# untitled.net
KiCad netlist of a schematic drawn in EAGLE
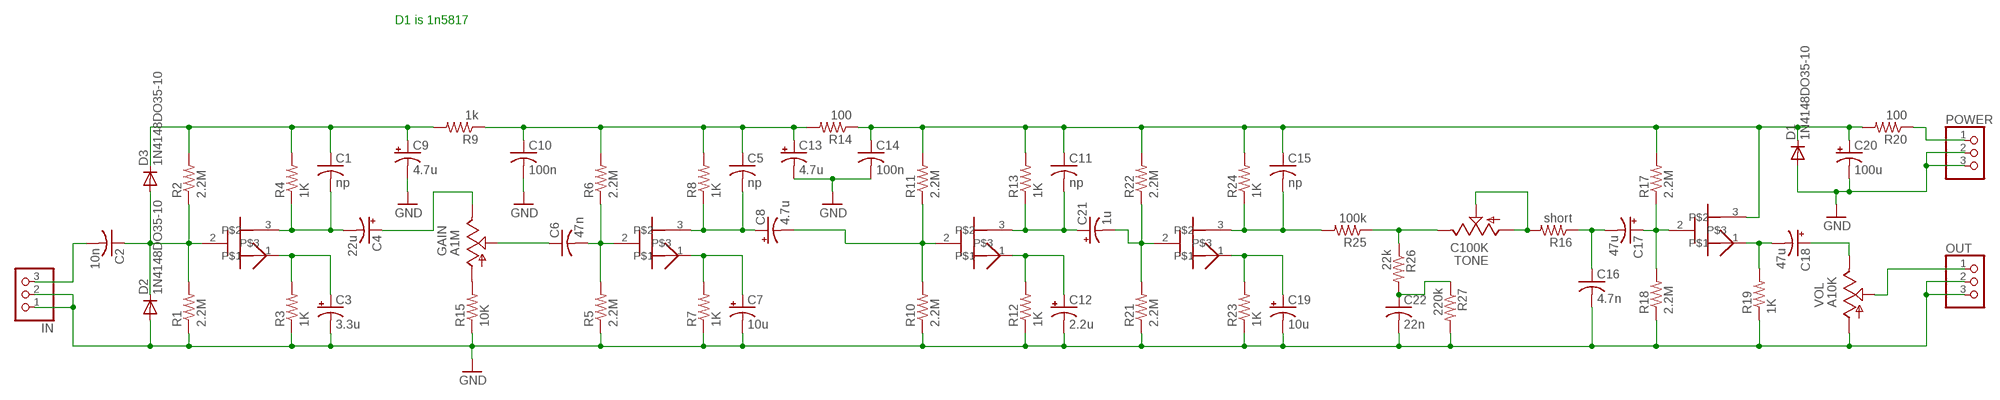
[diagram p0: schematic, sheet 1]

(export (version "E")
  (design (tool "Eeschema 10.0.6"))
  (components
    (comp (ref "C1")
      (value "np")
      (footprint "eagle-import:C050-030X075")
      (libsource (lib "eagle-import") (part "C-US050-030X075"))
    )
    (comp (ref "C2")
      (value "10n")
      (footprint "eagle-import:C050-030X075")
      (libsource (lib "eagle-import") (part "C-US050-030X075"))
    )
    (comp (ref "C3")
      (value "3.3u")
      (footprint "eagle-import:E2-5")
      (libsource (lib "eagle-import") (part "CPOL-USE2-5"))
    )
    (comp (ref "C4")
      (value "22u")
      (footprint "eagle-import:E2-5")
      (libsource (lib "eagle-import") (part "CPOL-USE2-5"))
    )
    (comp (ref "C5")
      (value "np")
      (footprint "eagle-import:C050-030X075")
      (libsource (lib "eagle-import") (part "C-US050-030X075"))
    )
    (comp (ref "C6")
      (value "47n")
      (footprint "eagle-import:C050-030X075")
      (libsource (lib "eagle-import") (part "C-US050-030X075"))
    )
    (comp (ref "C7")
      (value "10u")
      (footprint "eagle-import:E2-5")
      (libsource (lib "eagle-import") (part "CPOL-USE2-5"))
    )
    (comp (ref "C8")
      (value "4.7u")
      (footprint "eagle-import:E2-5")
      (libsource (lib "eagle-import") (part "CPOL-USE2-5"))
    )
    (comp (ref "C9")
      (value "4.7u")
      (footprint "eagle-import:E2-5")
      (libsource (lib "eagle-import") (part "CPOL-USE2-5"))
    )
    (comp (ref "C10")
      (value "100n")
      (footprint "eagle-import:C050-030X075")
      (libsource (lib "eagle-import") (part "C-US050-030X075"))
    )
    (comp (ref "C11")
      (value "np")
      (footprint "eagle-import:C050-030X075")
      (libsource (lib "eagle-import") (part "C-US050-030X075"))
    )
    (comp (ref "C12")
      (value "2.2u")
      (footprint "eagle-import:E2-5")
      (libsource (lib "eagle-import") (part "CPOL-USE2-5"))
    )
    (comp (ref "C13")
      (value "4.7u")
      (footprint "eagle-import:E2-5")
      (libsource (lib "eagle-import") (part "CPOL-USE2-5"))
    )
    (comp (ref "C14")
      (value "100n")
      (footprint "eagle-import:C050-030X075")
      (libsource (lib "eagle-import") (part "C-US050-030X075"))
    )
    (comp (ref "C15")
      (value "np")
      (footprint "eagle-import:C050-030X075")
      (libsource (lib "eagle-import") (part "C-US050-030X075"))
    )
    (comp (ref "C16")
      (value "4.7n")
      (footprint "eagle-import:C050-030X075")
      (libsource (lib "eagle-import") (part "C-US050-030X075"))
    )
    (comp (ref "C17")
      (value "47u")
      (footprint "eagle-import:E2-5")
      (libsource (lib "eagle-import") (part "CPOL-USE2-5"))
    )
    (comp (ref "C18")
      (value "47u")
      (footprint "eagle-import:E2-5")
      (libsource (lib "eagle-import") (part "CPOL-USE2-5"))
    )
    (comp (ref "C19")
      (value "10u")
      (footprint "eagle-import:E2-5")
      (libsource (lib "eagle-import") (part "CPOL-USE2-5"))
    )
    (comp (ref "C20")
      (value "100u")
      (footprint "eagle-import:E2-5")
      (libsource (lib "eagle-import") (part "CPOL-USE2-5"))
    )
    (comp (ref "C21")
      (value "1u")
      (footprint "eagle-import:E2-5")
      (libsource (lib "eagle-import") (part "CPOL-USE2-5"))
    )
    (comp (ref "C22")
      (value "22n")
      (footprint "eagle-import:C050-030X075")
      (libsource (lib "eagle-import") (part "C-US050-030X075"))
    )
    (comp (ref "D1")
      (value "1N4148DO35-10")
      (footprint "eagle-import:DO35-10")
      (libsource (lib "eagle-import") (part "1N4148DO35-10"))
    )
    (comp (ref "D2")
      (value "1N4148DO35-10")
      (footprint "eagle-import:DO35-10")
      (libsource (lib "eagle-import") (part "1N4148DO35-10"))
    )
    (comp (ref "D3")
      (value "1N4148DO35-10")
      (footprint "eagle-import:DO35-10")
      (libsource (lib "eagle-import") (part "1N4148DO35-10"))
    )
    (comp (ref "GAIN")
      (value "A1M")
      (footprint "eagle-import:3RP_1610N")
      (libsource (lib "eagle-import") (part "PEDALPOT"))
    )
    (comp (ref "IN")
      (value "PINHD-1X3")
      (footprint "eagle-import:1X03")
      (libsource (lib "eagle-import") (part "PINHD-1X3"))
    )
    (comp (ref "OUT")
      (value "PINHD-1X3")
      (footprint "eagle-import:1X03")
      (libsource (lib "eagle-import") (part "PINHD-1X3"))
    )
    (comp (ref "POWER")
      (value "PINHD-1X3")
      (footprint "eagle-import:1X03")
      (libsource (lib "eagle-import") (part "PINHD-1X3"))
    )
    (comp (ref "R1")
      (value "2.2M")
      (footprint "eagle-import:0207_7")
      (libsource (lib "eagle-import") (part "R-US_0207/7"))
    )
    (comp (ref "R2")
      (value "2.2M")
      (footprint "eagle-import:0207_7")
      (libsource (lib "eagle-import") (part "R-US_0207/7"))
    )
    (comp (ref "R3")
      (value "1K")
      (footprint "eagle-import:0207_7")
      (libsource (lib "eagle-import") (part "R-US_0207/7"))
    )
    (comp (ref "R4")
      (value "1K")
      (footprint "eagle-import:0207_7")
      (libsource (lib "eagle-import") (part "R-US_0207/7"))
    )
    (comp (ref "R5")
      (value "2.2M")
      (footprint "eagle-import:0207_7")
      (libsource (lib "eagle-import") (part "R-US_0207/7"))
    )
    (comp (ref "R6")
      (value "2.2M")
      (footprint "eagle-import:0207_7")
      (libsource (lib "eagle-import") (part "R-US_0207/7"))
    )
    (comp (ref "R7")
      (value "1K")
      (footprint "eagle-import:0207_7")
      (libsource (lib "eagle-import") (part "R-US_0207/7"))
    )
    (comp (ref "R8")
      (value "1K")
      (footprint "eagle-import:0207_7")
      (libsource (lib "eagle-import") (part "R-US_0207/7"))
    )
    (comp (ref "R9")
      (value "1k")
      (footprint "eagle-import:0207_7")
      (libsource (lib "eagle-import") (part "R-US_0207/7"))
    )
    (comp (ref "R10")
      (value "2.2M")
      (footprint "eagle-import:0207_7")
      (libsource (lib "eagle-import") (part "R-US_0207/7"))
    )
    (comp (ref "R11")
      (value "2.2M")
      (footprint "eagle-import:0207_7")
      (libsource (lib "eagle-import") (part "R-US_0207/7"))
    )
    (comp (ref "R12")
      (value "1K")
      (footprint "eagle-import:0207_7")
      (libsource (lib "eagle-import") (part "R-US_0207/7"))
    )
    (comp (ref "R13")
      (value "1K")
      (footprint "eagle-import:0207_7")
      (libsource (lib "eagle-import") (part "R-US_0207/7"))
    )
    (comp (ref "R14")
      (value "100")
      (footprint "eagle-import:0207_7")
      (libsource (lib "eagle-import") (part "R-US_0207/7"))
    )
    (comp (ref "R15")
      (value "10K")
      (footprint "eagle-import:0207_7")
      (libsource (lib "eagle-import") (part "R-US_0207/7"))
    )
    (comp (ref "R16")
      (value "short")
      (footprint "eagle-import:0207_7")
      (libsource (lib "eagle-import") (part "R-US_0207/7"))
    )
    (comp (ref "R17")
      (value "2.2M")
      (footprint "eagle-import:0207_7")
      (libsource (lib "eagle-import") (part "R-US_0207/7"))
    )
    (comp (ref "R18")
      (value "2.2M")
      (footprint "eagle-import:0207_7")
      (libsource (lib "eagle-import") (part "R-US_0207/7"))
    )
    (comp (ref "R19")
      (value "1K")
      (footprint "eagle-import:0207_7")
      (libsource (lib "eagle-import") (part "R-US_0207/7"))
    )
    (comp (ref "R20")
      (value "100")
      (footprint "eagle-import:0207_7")
      (libsource (lib "eagle-import") (part "R-US_0207/7"))
    )
    (comp (ref "R21")
      (value "2.2M")
      (footprint "eagle-import:0207_7")
      (libsource (lib "eagle-import") (part "R-US_0207/7"))
    )
    (comp (ref "R22")
      (value "2.2M")
      (footprint "eagle-import:0207_7")
      (libsource (lib "eagle-import") (part "R-US_0207/7"))
    )
    (comp (ref "R23")
      (value "1K")
      (footprint "eagle-import:0207_7")
      (libsource (lib "eagle-import") (part "R-US_0207/7"))
    )
    (comp (ref "R24")
      (value "1K")
      (footprint "eagle-import:0207_7")
      (libsource (lib "eagle-import") (part "R-US_0207/7"))
    )
    (comp (ref "R25")
      (value "100k")
      (footprint "eagle-import:0207_7")
      (libsource (lib "eagle-import") (part "R-US_0207/7"))
    )
    (comp (ref "R26")
      (value "22k")
      (footprint "eagle-import:0207_7")
      (libsource (lib "eagle-import") (part "R-US_0207/7"))
    )
    (comp (ref "R27")
      (value "220k")
      (footprint "eagle-import:0207_7")
      (libsource (lib "eagle-import") (part "R-US_0207/7"))
    )
    (comp (ref "TONE")
      (value "C100K")
      (footprint "eagle-import:3RP_1610N")
      (libsource (lib "eagle-import") (part "PEDALPOT"))
    )
    (comp (ref "U$1")
      (value "2N7000_2")
      (footprint "eagle-import:TO92")
      (libsource (lib "eagle-import") (part "2N7000_2"))
    )
    (comp (ref "U$2")
      (value "2N7000_2")
      (footprint "eagle-import:TO92")
      (libsource (lib "eagle-import") (part "2N7000_2"))
    )
    (comp (ref "U$3")
      (value "2N7000_2")
      (footprint "eagle-import:TO92")
      (libsource (lib "eagle-import") (part "2N7000_2"))
    )
    (comp (ref "U$4")
      (value "2N7000_2")
      (footprint "eagle-import:TO92")
      (libsource (lib "eagle-import") (part "2N7000_2"))
    )
    (comp (ref "U$5")
      (value "2N7000_2")
      (footprint "eagle-import:TO92")
      (libsource (lib "eagle-import") (part "2N7000_2"))
    )
    (comp (ref "VOL")
      (value "A10K")
      (footprint "eagle-import:3RP_1610N")
      (libsource (lib "eagle-import") (part "PEDALPOT"))
    )
  )
  (nets
    (net (code "1") (name "GND") (class "Default")
      (node (ref "C10") (pin "2") (pinfunction "2_2") (pintype "passive"))
      (node (ref "C12") (pin "-") (pinfunction "-_-") (pintype "passive"))
      (node (ref "C13") (pin "-") (pinfunction "-_-") (pintype "passive"))
      (node (ref "C14") (pin "2") (pinfunction "2_2") (pintype "passive"))
      (node (ref "C16") (pin "2") (pinfunction "2_2") (pintype "passive"))
      (node (ref "C19") (pin "-") (pinfunction "-_-") (pintype "passive"))
      (node (ref "C20") (pin "-") (pinfunction "-_-") (pintype "passive"))
      (node (ref "C22") (pin "2") (pinfunction "2_2") (pintype "passive"))
      (node (ref "C3") (pin "-") (pinfunction "-_-") (pintype "passive"))
      (node (ref "C7") (pin "-") (pinfunction "-_-") (pintype "passive"))
      (node (ref "C9") (pin "-") (pinfunction "-_-") (pintype "passive"))
      (node (ref "D1") (pin "A") (pinfunction "A_A") (pintype "passive"))
      (node (ref "D2") (pin "A") (pinfunction "A_A") (pintype "passive"))
      (node (ref "IN") (pin "1") (pinfunction "1_1") (pintype "passive"))
      (node (ref "IN") (pin "2") (pinfunction "2_2") (pintype "passive"))
      (node (ref "OUT") (pin "2") (pinfunction "2_2") (pintype "passive"))
      (node (ref "OUT") (pin "3") (pinfunction "3_3") (pintype "passive"))
      (node (ref "POWER") (pin "2") (pinfunction "2_2") (pintype "passive"))
      (node (ref "POWER") (pin "3") (pinfunction "3_3") (pintype "passive"))
      (node (ref "R1") (pin "1") (pinfunction "1_1") (pintype "passive"))
      (node (ref "R10") (pin "1") (pinfunction "1_1") (pintype "passive"))
      (node (ref "R12") (pin "1") (pinfunction "1_1") (pintype "passive"))
      (node (ref "R15") (pin "1") (pinfunction "1_1") (pintype "passive"))
      (node (ref "R18") (pin "1") (pinfunction "1_1") (pintype "passive"))
      (node (ref "R19") (pin "1") (pinfunction "1_1") (pintype "passive"))
      (node (ref "R21") (pin "1") (pinfunction "1_1") (pintype "passive"))
      (node (ref "R23") (pin "1") (pinfunction "1_1") (pintype "passive"))
      (node (ref "R27") (pin "2") (pinfunction "2_2") (pintype "passive"))
      (node (ref "R3") (pin "1") (pinfunction "1_1") (pintype "passive"))
      (node (ref "R5") (pin "1") (pinfunction "1_1") (pintype "passive"))
      (node (ref "R7") (pin "1") (pinfunction "1_1") (pintype "passive"))
      (node (ref "VOL") (pin "3") (pinfunction "A_3") (pintype "passive"))
    )
    (net (code "2") (name "Net-(C1-Pad1)") (class "Default")
      (node (ref "C1") (pin "1") (pinfunction "1_1") (pintype "passive"))
      (node (ref "C9") (pin "+") (pinfunction "+_+") (pintype "passive"))
      (node (ref "D3") (pin "C") (pinfunction "C_C") (pintype "passive"))
      (node (ref "R2") (pin "2") (pinfunction "2_2") (pintype "passive"))
      (node (ref "R4") (pin "2") (pinfunction "2_2") (pintype "passive"))
      (node (ref "R9") (pin "2") (pinfunction "2_2") (pintype "passive"))
    )
    (net (code "3") (name "Net-(C2-Pad2)") (class "Default")
      (node (ref "C2") (pin "2") (pinfunction "2_2") (pintype "passive"))
      (node (ref "IN") (pin "3") (pinfunction "3_3") (pintype "passive"))
    )
    (net (code "4") (name "Net-(C10-Pad1)") (class "Default")
      (node (ref "C10") (pin "1") (pinfunction "1_1") (pintype "passive"))
      (node (ref "C13") (pin "+") (pinfunction "+_+") (pintype "passive"))
      (node (ref "C5") (pin "1") (pinfunction "1_1") (pintype "passive"))
      (node (ref "R14") (pin "2") (pinfunction "2_2") (pintype "passive"))
      (node (ref "R6") (pin "2") (pinfunction "2_2") (pintype "passive"))
      (node (ref "R8") (pin "2") (pinfunction "2_2") (pintype "passive"))
      (node (ref "R9") (pin "1") (pinfunction "1_1") (pintype "passive"))
    )
    (net (code "5") (name "Net-(C16-Pad1)") (class "Default")
      (node (ref "C16") (pin "1") (pinfunction "1_1") (pintype "passive"))
      (node (ref "C17") (pin "-") (pinfunction "-_-") (pintype "passive"))
      (node (ref "R16") (pin "1") (pinfunction "1_1") (pintype "passive"))
    )
    (net (code "6") (name "Net-(C22-Pad1)") (class "Default")
      (node (ref "C22") (pin "1") (pinfunction "1_1") (pintype "passive"))
      (node (ref "R26") (pin "2") (pinfunction "2_2") (pintype "passive"))
      (node (ref "R27") (pin "1") (pinfunction "1_1") (pintype "passive"))
    )
    (net (code "7") (name "Net-(GAIN-A)") (class "Default")
      (node (ref "GAIN") (pin "3") (pinfunction "A_3") (pintype "passive"))
      (node (ref "R15") (pin "2") (pinfunction "2_2") (pintype "passive"))
    )
    (net (code "8") (name "Net-(GAIN-E)") (class "Default")
      (node (ref "C4") (pin "+") (pinfunction "+_+") (pintype "passive"))
      (node (ref "GAIN") (pin "1") (pinfunction "E_1") (pintype "passive"))
    )
    (net (code "9") (name "Net-(GAIN-S)") (class "Default")
      (node (ref "C6") (pin "1") (pinfunction "1_1") (pintype "passive"))
      (node (ref "GAIN") (pin "2") (pinfunction "S_2") (pintype "passive"))
    )
    (net (code "10") (name "Net-(POWER-Pad1)") (class "Default")
      (node (ref "POWER") (pin "1") (pinfunction "1_1") (pintype "passive"))
      (node (ref "R20") (pin "1") (pinfunction "1_1") (pintype "passive"))
    )
    (net (code "11") (name "Net-(TONE-A)") (class "Default")
      (node (ref "R16") (pin "2") (pinfunction "2_2") (pintype "passive"))
      (node (ref "TONE") (pin "2") (pinfunction "S_2") (pintype "passive"))
      (node (ref "TONE") (pin "3") (pinfunction "A_3") (pintype "passive"))
    )
    (net (code "12") (name "Net-(TONE-E)") (class "Default")
      (node (ref "R25") (pin "1") (pinfunction "1_1") (pintype "passive"))
      (node (ref "R26") (pin "1") (pinfunction "1_1") (pintype "passive"))
      (node (ref "TONE") (pin "1") (pinfunction "E_1") (pintype "passive"))
    )
    (net (code "13") (name "Net-(U$1-P$1)") (class "Default")
      (node (ref "C3") (pin "+") (pinfunction "+_+") (pintype "passive"))
      (node (ref "R3") (pin "2") (pinfunction "2_2") (pintype "passive"))
      (node (ref "U$1") (pin "1") (pinfunction "P$1_1") (pintype "bidirectional"))
    )
    (net (code "14") (name "Net-(U$1-P$2)") (class "Default")
      (node (ref "C1") (pin "2") (pinfunction "2_2") (pintype "passive"))
      (node (ref "C4") (pin "-") (pinfunction "-_-") (pintype "passive"))
      (node (ref "R4") (pin "1") (pinfunction "1_1") (pintype "passive"))
      (node (ref "U$1") (pin "3") (pinfunction "P$2_3") (pintype "bidirectional"))
    )
    (net (code "15") (name "Net-(U$1-P$3)") (class "Default")
      (node (ref "C2") (pin "1") (pinfunction "1_1") (pintype "passive"))
      (node (ref "D2") (pin "C") (pinfunction "C_C") (pintype "passive"))
      (node (ref "D3") (pin "A") (pinfunction "A_A") (pintype "passive"))
      (node (ref "R1") (pin "2") (pinfunction "2_2") (pintype "passive"))
      (node (ref "R2") (pin "1") (pinfunction "1_1") (pintype "passive"))
      (node (ref "U$1") (pin "2") (pinfunction "P$3_2") (pintype "bidirectional"))
    )
    (net (code "16") (name "Net-(U$2-P$1)") (class "Default")
      (node (ref "C7") (pin "+") (pinfunction "+_+") (pintype "passive"))
      (node (ref "R7") (pin "2") (pinfunction "2_2") (pintype "passive"))
      (node (ref "U$2") (pin "1") (pinfunction "P$1_1") (pintype "bidirectional"))
    )
    (net (code "17") (name "Net-(U$2-P$2)") (class "Default")
      (node (ref "C5") (pin "2") (pinfunction "2_2") (pintype "passive"))
      (node (ref "C8") (pin "+") (pinfunction "+_+") (pintype "passive"))
      (node (ref "R8") (pin "1") (pinfunction "1_1") (pintype "passive"))
      (node (ref "U$2") (pin "3") (pinfunction "P$2_3") (pintype "bidirectional"))
    )
    (net (code "18") (name "Net-(U$2-P$3)") (class "Default")
      (node (ref "C6") (pin "2") (pinfunction "2_2") (pintype "passive"))
      (node (ref "R5") (pin "2") (pinfunction "2_2") (pintype "passive"))
      (node (ref "R6") (pin "1") (pinfunction "1_1") (pintype "passive"))
      (node (ref "U$2") (pin "2") (pinfunction "P$3_2") (pintype "bidirectional"))
    )
    (net (code "19") (name "Net-(U$3-P$1)") (class "Default")
      (node (ref "C12") (pin "+") (pinfunction "+_+") (pintype "passive"))
      (node (ref "R12") (pin "2") (pinfunction "2_2") (pintype "passive"))
      (node (ref "U$3") (pin "1") (pinfunction "P$1_1") (pintype "bidirectional"))
    )
    (net (code "20") (name "Net-(U$3-P$2)") (class "Default")
      (node (ref "C11") (pin "2") (pinfunction "2_2") (pintype "passive"))
      (node (ref "C21") (pin "+") (pinfunction "+_+") (pintype "passive"))
      (node (ref "R13") (pin "1") (pinfunction "1_1") (pintype "passive"))
      (node (ref "U$3") (pin "3") (pinfunction "P$2_3") (pintype "bidirectional"))
    )
    (net (code "21") (name "Net-(U$3-P$3)") (class "Default")
      (node (ref "C8") (pin "-") (pinfunction "-_-") (pintype "passive"))
      (node (ref "R10") (pin "2") (pinfunction "2_2") (pintype "passive"))
      (node (ref "R11") (pin "1") (pinfunction "1_1") (pintype "passive"))
      (node (ref "U$3") (pin "2") (pinfunction "P$3_2") (pintype "bidirectional"))
    )
    (net (code "22") (name "Net-(U$4-P$1)") (class "Default")
      (node (ref "C18") (pin "-") (pinfunction "-_-") (pintype "passive"))
      (node (ref "R19") (pin "2") (pinfunction "2_2") (pintype "passive"))
      (node (ref "U$4") (pin "1") (pinfunction "P$1_1") (pintype "bidirectional"))
    )
    (net (code "23") (name "Net-(U$4-P$2)") (class "Default")
      (node (ref "C11") (pin "1") (pinfunction "1_1") (pintype "passive"))
      (node (ref "C14") (pin "1") (pinfunction "1_1") (pintype "passive"))
      (node (ref "C15") (pin "1") (pinfunction "1_1") (pintype "passive"))
      (node (ref "C20") (pin "+") (pinfunction "+_+") (pintype "passive"))
      (node (ref "D1") (pin "C") (pinfunction "C_C") (pintype "passive"))
      (node (ref "R11") (pin "2") (pinfunction "2_2") (pintype "passive"))
      (node (ref "R13") (pin "2") (pinfunction "2_2") (pintype "passive"))
      (node (ref "R14") (pin "1") (pinfunction "1_1") (pintype "passive"))
      (node (ref "R17") (pin "2") (pinfunction "2_2") (pintype "passive"))
      (node (ref "R20") (pin "2") (pinfunction "2_2") (pintype "passive"))
      (node (ref "R22") (pin "2") (pinfunction "2_2") (pintype "passive"))
      (node (ref "R24") (pin "2") (pinfunction "2_2") (pintype "passive"))
      (node (ref "U$4") (pin "3") (pinfunction "P$2_3") (pintype "bidirectional"))
    )
    (net (code "24") (name "Net-(U$4-P$3)") (class "Default")
      (node (ref "C17") (pin "+") (pinfunction "+_+") (pintype "passive"))
      (node (ref "R17") (pin "1") (pinfunction "1_1") (pintype "passive"))
      (node (ref "R18") (pin "2") (pinfunction "2_2") (pintype "passive"))
      (node (ref "U$4") (pin "2") (pinfunction "P$3_2") (pintype "bidirectional"))
    )
    (net (code "25") (name "Net-(U$5-P$1)") (class "Default")
      (node (ref "C19") (pin "+") (pinfunction "+_+") (pintype "passive"))
      (node (ref "R23") (pin "2") (pinfunction "2_2") (pintype "passive"))
      (node (ref "U$5") (pin "1") (pinfunction "P$1_1") (pintype "bidirectional"))
    )
    (net (code "26") (name "Net-(U$5-P$2)") (class "Default")
      (node (ref "C15") (pin "2") (pinfunction "2_2") (pintype "passive"))
      (node (ref "R24") (pin "1") (pinfunction "1_1") (pintype "passive"))
      (node (ref "R25") (pin "2") (pinfunction "2_2") (pintype "passive"))
      (node (ref "U$5") (pin "3") (pinfunction "P$2_3") (pintype "bidirectional"))
    )
    (net (code "27") (name "Net-(U$5-P$3)") (class "Default")
      (node (ref "C21") (pin "-") (pinfunction "-_-") (pintype "passive"))
      (node (ref "R21") (pin "2") (pinfunction "2_2") (pintype "passive"))
      (node (ref "R22") (pin "1") (pinfunction "1_1") (pintype "passive"))
      (node (ref "U$5") (pin "2") (pinfunction "P$3_2") (pintype "bidirectional"))
    )
    (net (code "28") (name "Net-(VOL-E)") (class "Default")
      (node (ref "C18") (pin "+") (pinfunction "+_+") (pintype "passive"))
      (node (ref "VOL") (pin "1") (pinfunction "E_1") (pintype "passive"))
    )
    (net (code "29") (name "Net-(VOL-S)") (class "Default")
      (node (ref "OUT") (pin "1") (pinfunction "1_1") (pintype "passive"))
      (node (ref "VOL") (pin "2") (pinfunction "S_2") (pintype "passive"))
    )
  )
)
